# schematic.net
KiCad netlist of a schematic drawn in EAGLE
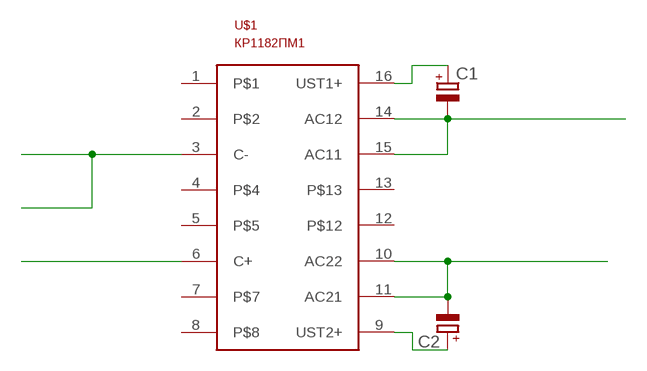
[diagram p0: schematic, sheet 1]

(export (version "E")
  (design (tool "Eeschema 10.0.6"))
  (components
    (comp (ref "C1")
      (value "CPOL-EUE2.5-5")
      (footprint "eagle-import:E2,5-5")
      (libsource (lib "eagle-import") (part "CPOL-EUE2.5-5"))
    )
    (comp (ref "C2")
      (value "CPOL-EUE2.5-5")
      (footprint "eagle-import:E2,5-5")
      (libsource (lib "eagle-import") (part "CPOL-EUE2.5-5"))
    )
    (comp (ref "U$1")
      (value "КР1182ПМ1")
      (footprint "eagle-import:DIL16")
      (libsource (lib "eagle-import") (part "КР1182ПМ1"))
    )
  )
  (nets
    (net (code "1") (name "Net-(U$1-AC11)") (class "Default")
      (node (ref "C1") (pin "-") (pinfunction "-_-") (pintype "passive"))
      (node (ref "U$1") (pin "14") (pinfunction "AC12_14") (pintype "power_in"))
      (node (ref "U$1") (pin "15") (pinfunction "AC11_15") (pintype "power_in"))
    )
    (net (code "2") (name "Net-(U$1-AC21)") (class "Default")
      (node (ref "C2") (pin "-") (pinfunction "-_-") (pintype "passive"))
      (node (ref "U$1") (pin "10") (pinfunction "AC22_10") (pintype "power_in"))
      (node (ref "U$1") (pin "11") (pinfunction "AC21_11") (pintype "power_in"))
    )
    (net (code "3") (name "Net-(U$1-UST1+)") (class "Default")
      (node (ref "C1") (pin "+") (pinfunction "+_+") (pintype "passive"))
      (node (ref "U$1") (pin "16") (pinfunction "UST1+_16") (pintype "power_in"))
    )
    (net (code "4") (name "Net-(U$1-UST2+)") (class "Default")
      (node (ref "C2") (pin "+") (pinfunction "+_+") (pintype "passive"))
      (node (ref "U$1") (pin "9") (pinfunction "UST2+_9") (pintype "power_in"))
    )
    (net (code "5") (name "unconnected-(U$1-C+-Pad6)") (class "Default")
      (node (ref "U$1") (pin "6") (pinfunction "C+_6") (pintype "bidirectional"))
    )
    (net (code "6") (name "unconnected-(U$1-C--Pad3)") (class "Default")
      (node (ref "U$1") (pin "3") (pinfunction "C-_3") (pintype "bidirectional"))
    )
    (net (code "7") (name "unconnected-(U$1-P$1-Pad1)") (class "Default")
      (node (ref "U$1") (pin "1") (pinfunction "P$1_1") (pintype "no_connect"))
    )
    (net (code "8") (name "unconnected-(U$1-P$2-Pad2)") (class "Default")
      (node (ref "U$1") (pin "2") (pinfunction "P$2_2") (pintype "no_connect"))
    )
    (net (code "9") (name "unconnected-(U$1-P$4-Pad4)") (class "Default")
      (node (ref "U$1") (pin "4") (pinfunction "P$4_4") (pintype "no_connect"))
    )
    (net (code "10") (name "unconnected-(U$1-P$5-Pad5)") (class "Default")
      (node (ref "U$1") (pin "5") (pinfunction "P$5_5") (pintype "no_connect"))
    )
    (net (code "11") (name "unconnected-(U$1-P$7-Pad7)") (class "Default")
      (node (ref "U$1") (pin "7") (pinfunction "P$7_7") (pintype "no_connect"))
    )
    (net (code "12") (name "unconnected-(U$1-P$8-Pad8)") (class "Default")
      (node (ref "U$1") (pin "8") (pinfunction "P$8_8") (pintype "no_connect"))
    )
    (net (code "13") (name "unconnected-(U$1-P$12-Pad12)") (class "Default")
      (node (ref "U$1") (pin "12") (pinfunction "P$12_12") (pintype "no_connect"))
    )
    (net (code "14") (name "unconnected-(U$1-P$13-Pad13)") (class "Default")
      (node (ref "U$1") (pin "13") (pinfunction "P$13_13") (pintype "no_connect"))
    )
  )
)
